# Schematic_ESPHome_P1_Gateway_working_des.net
KiCad netlist of a schematic drawn in EasyEDA
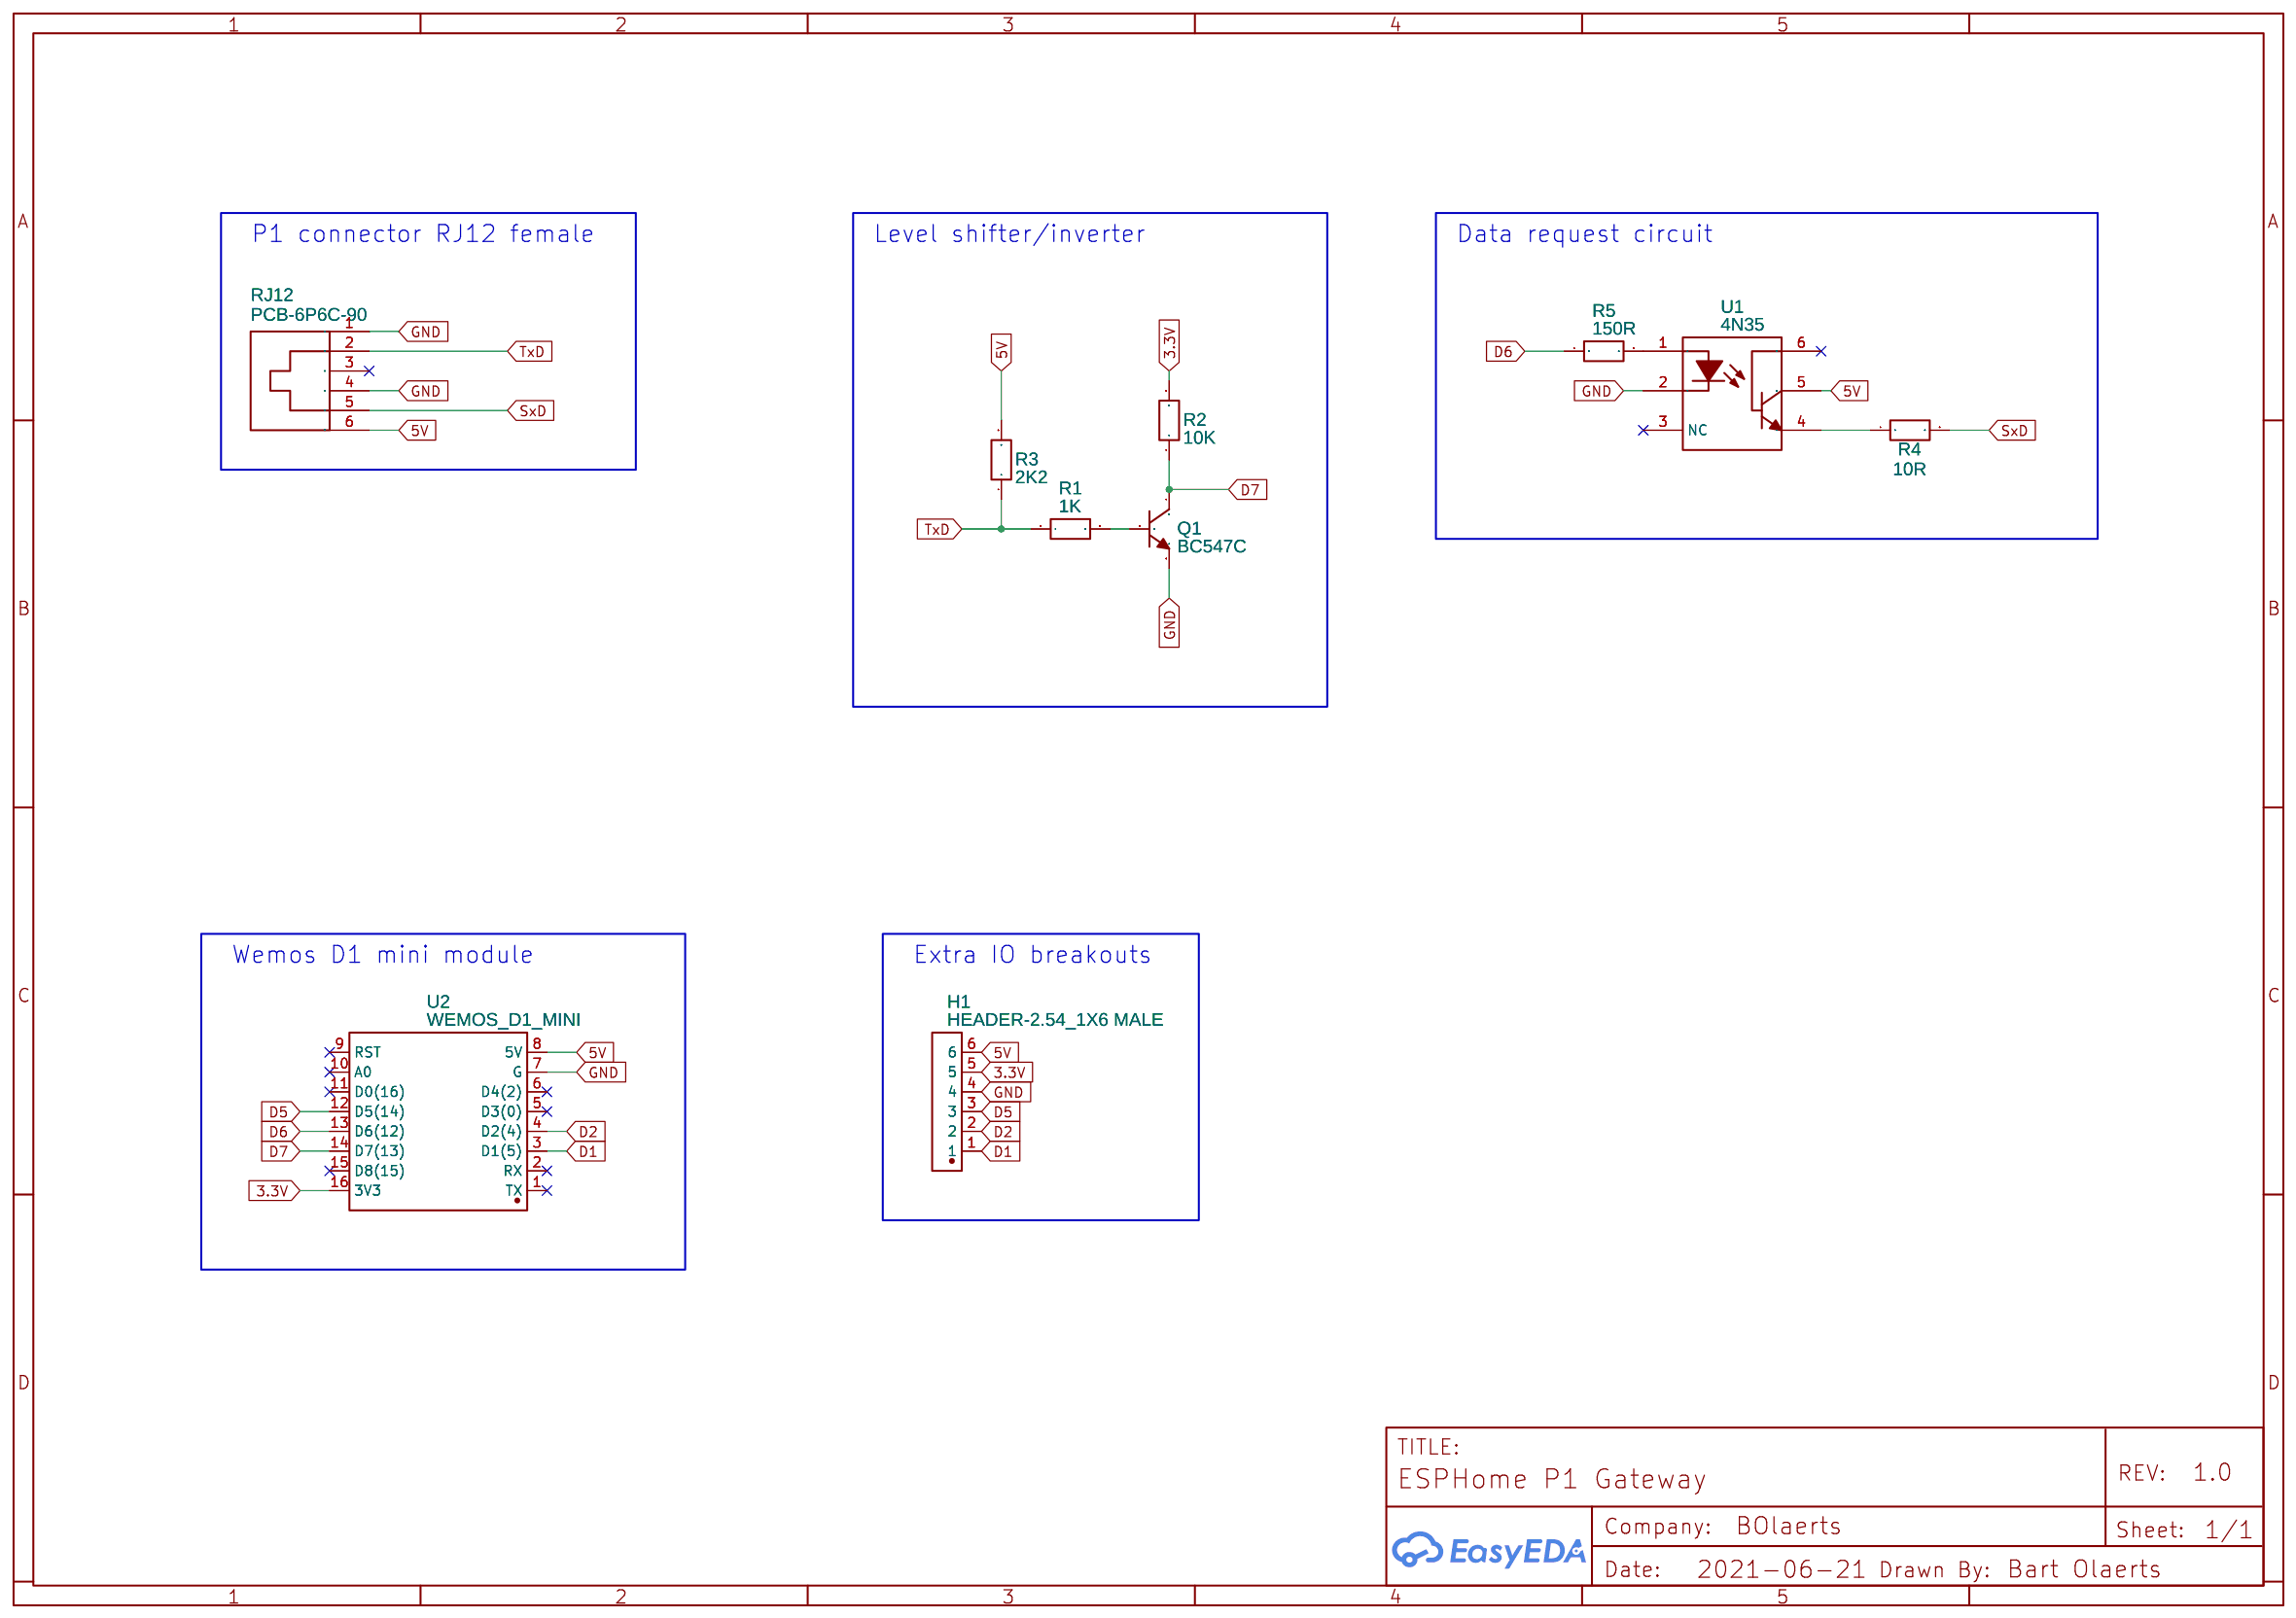
[diagram p0: schematic sheet]

(export (version "E")
  (design (tool "Eeschema 10.0.6"))
  (components
    (comp (ref "H1")
      (value "HEADER-2.54_1X6 MALE")
      (fields
        (field (name "BOM_Manufacturer Part") "Z-211-0411-0021-001")
        (field (name "BOM_Supplier Part") "C152150")
      )
      (libsource (lib "") (part "HEADER-2.54_1X6 MALE"))
    )
    (comp (ref "Q1")
      (value "BC547C")
      (fields (field (name "BOM_Supplier Part") "C713614"))
      (libsource (lib "") (part "BC547C"))
    )
    (comp (ref "R1")
      (value "1K")
      (fields
        (field (name "BOM_Manufacturer Part") "RD 1/2WS 10K J T/B A1")
        (field (name "BOM_Supplier Part") "C433797")
      )
      (libsource (lib "") (part "RD 1/2WS 10K J T/B A1"))
    )
    (comp (ref "R2")
      (value "10K")
      (fields
        (field (name "BOM_Manufacturer Part") "RD 1/2WS 10K J T/B A1")
        (field (name "BOM_Supplier Part") "C433797")
      )
      (libsource (lib "") (part "RD 1/2WS 10K J T/B A1_1"))
    )
    (comp (ref "R3")
      (value "2K2")
      (fields
        (field (name "BOM_Manufacturer Part") "RD 1/2WS 10K J T/B A1")
        (field (name "BOM_Supplier Part") "C433797")
      )
      (libsource (lib "") (part "RD 1/2WS 10K J T/B A1_1"))
    )
    (comp (ref "R4")
      (value "10R")
      (fields
        (field (name "BOM_Manufacturer Part") "RD 1/2WS 10K J T/B A1")
        (field (name "BOM_Supplier Part") "C433797")
      )
      (libsource (lib "") (part "RD 1/2WS 10K J T/B A1"))
    )
    (comp (ref "R5")
      (value "150R")
      (fields
        (field (name "BOM_Manufacturer Part") "RD 1/2WS 10K J T/B A1")
        (field (name "BOM_Supplier Part") "C433797")
      )
      (libsource (lib "") (part "RD 1/2WS 10K J T/B A1"))
    )
    (comp (ref "RJ12")
      (value "PCB-6P6C-90")
      (fields (field (name "BOM_Supplier Part") "C189750"))
      (libsource (lib "") (part "PCB-6P6C-90"))
    )
    (comp (ref "U1")
      (value "4N35")
      (fields (field (name "BOM_Supplier Part") "C57084"))
      (libsource (lib "") (part "4N35"))
    )
    (comp (ref "U2")
      (value "WEMOS_D1_MINI")
      (fields
        (field (name "BOM_Manufacturer Part") "Wemos_D1_mini_Pro4")
        (field (name "BOM_Supplier Part") "C2837266")
      )
      (libsource (lib "") (part "WEMOS_D1_MINI_PRO4"))
    )
  )
  (nets
    (net (code "1") (name "3.3V") (class "Default")
      (node (ref "H1") (pin "5") (pinfunction "5_5") (pintype "unspecified"))
      (node (ref "R2") (pin "2") (pinfunction "2_2") (pintype "unspecified"))
      (node (ref "U2") (pin "16") (pinfunction "3V3_16") (pintype "unspecified"))
    )
    (net (code "2") (name "5V") (class "Default")
      (node (ref "H1") (pin "6") (pinfunction "6_6") (pintype "unspecified"))
      (node (ref "R3") (pin "2") (pinfunction "2_2") (pintype "unspecified"))
      (node (ref "RJ12") (pin "6") (pinfunction "6_6") (pintype "unspecified"))
      (node (ref "U1") (pin "5") (pinfunction "5_5") (pintype "unspecified"))
      (node (ref "U2") (pin "8") (pinfunction "5V_8") (pintype "unspecified"))
    )
    (net (code "3") (name "D1") (class "Default")
      (node (ref "H1") (pin "1") (pinfunction "1_1") (pintype "unspecified"))
      (node (ref "U2") (pin "3") (pinfunction "D1(5)_3") (pintype "unspecified"))
    )
    (net (code "4") (name "D2") (class "Default")
      (node (ref "H1") (pin "2") (pinfunction "2_2") (pintype "unspecified"))
      (node (ref "U2") (pin "4") (pinfunction "D2(4)_4") (pintype "unspecified"))
    )
    (net (code "5") (name "D5") (class "Default")
      (node (ref "H1") (pin "3") (pinfunction "3_3") (pintype "unspecified"))
      (node (ref "U2") (pin "12") (pinfunction "D5(14)_12") (pintype "unspecified"))
    )
    (net (code "6") (name "D6") (class "Default")
      (node (ref "R5") (pin "1") (pinfunction "1_1") (pintype "unspecified"))
      (node (ref "U2") (pin "13") (pinfunction "D6(12)_13") (pintype "unspecified"))
    )
    (net (code "7") (name "D7") (class "Default")
      (node (ref "Q1") (pin "1") (pinfunction "C_1") (pintype "input"))
      (node (ref "R2") (pin "1") (pinfunction "1_1") (pintype "unspecified"))
      (node (ref "U2") (pin "14") (pinfunction "D7(13)_14") (pintype "unspecified"))
    )
    (net (code "8") (name "GND") (class "Default")
      (node (ref "H1") (pin "4") (pinfunction "4_4") (pintype "unspecified"))
      (node (ref "Q1") (pin "3") (pinfunction "E_3") (pintype "input"))
      (node (ref "RJ12") (pin "1") (pinfunction "1_1") (pintype "unspecified"))
      (node (ref "RJ12") (pin "4") (pinfunction "4_4") (pintype "unspecified"))
      (node (ref "U1") (pin "2") (pinfunction "2_2") (pintype "unspecified"))
      (node (ref "U2") (pin "7") (pinfunction "G_7") (pintype "unspecified"))
    )
    (net (code "9") (name "Net-(Q1-B)") (class "Default")
      (node (ref "Q1") (pin "2") (pinfunction "B_2") (pintype "input"))
      (node (ref "R1") (pin "2") (pinfunction "2_2") (pintype "unspecified"))
    )
    (net (code "10") (name "Net-(R4-Pad1)") (class "Default")
      (node (ref "R4") (pin "1") (pinfunction "1_1") (pintype "unspecified"))
      (node (ref "U1") (pin "4") (pinfunction "4_4") (pintype "unspecified"))
    )
    (net (code "11") (name "Net-(R5-Pad2)") (class "Default")
      (node (ref "R5") (pin "2") (pinfunction "2_2") (pintype "unspecified"))
      (node (ref "U1") (pin "1") (pinfunction "1_1") (pintype "unspecified"))
    )
    (net (code "12") (name "SxD") (class "Default")
      (node (ref "R4") (pin "2") (pinfunction "2_2") (pintype "unspecified"))
      (node (ref "RJ12") (pin "5") (pinfunction "5_5") (pintype "unspecified"))
    )
    (net (code "13") (name "TxD") (class "Default")
      (node (ref "R1") (pin "1") (pinfunction "1_1") (pintype "unspecified"))
      (node (ref "R3") (pin "1") (pinfunction "1_1") (pintype "unspecified"))
      (node (ref "RJ12") (pin "2") (pinfunction "2_2") (pintype "unspecified"))
    )
    (net (code "14") (name "unconnected-(RJ12-Pad3)") (class "Default")
      (node (ref "RJ12") (pin "3") (pinfunction "3_3") (pintype "unspecified+no_connect"))
    )
    (net (code "15") (name "unconnected-(U1-NC-Pad3)") (class "Default")
      (node (ref "U1") (pin "3") (pinfunction "NC_3") (pintype "unspecified+no_connect"))
    )
    (net (code "16") (name "unconnected-(U1-Pad6)") (class "Default")
      (node (ref "U1") (pin "6") (pinfunction "6_6") (pintype "unspecified+no_connect"))
    )
    (net (code "17") (name "unconnected-(U2-A0-Pad10)") (class "Default")
      (node (ref "U2") (pin "10") (pinfunction "A0_10") (pintype "unspecified+no_connect"))
    )
    (net (code "18") (name "unconnected-(U2-D0(16)-Pad11)") (class "Default")
      (node (ref "U2") (pin "11") (pinfunction "D0(16)_11") (pintype "unspecified+no_connect"))
    )
    (net (code "19") (name "unconnected-(U2-D3(0)-Pad5)") (class "Default")
      (node (ref "U2") (pin "5") (pinfunction "D3(0)_5") (pintype "unspecified+no_connect"))
    )
    (net (code "20") (name "unconnected-(U2-D4(2)-Pad6)") (class "Default")
      (node (ref "U2") (pin "6") (pinfunction "D4(2)_6") (pintype "unspecified+no_connect"))
    )
    (net (code "21") (name "unconnected-(U2-D8(15)-Pad15)") (class "Default")
      (node (ref "U2") (pin "15") (pinfunction "D8(15)_15") (pintype "unspecified+no_connect"))
    )
    (net (code "22") (name "unconnected-(U2-RST-Pad9)") (class "Default")
      (node (ref "U2") (pin "9") (pinfunction "RST_9") (pintype "unspecified+no_connect"))
    )
    (net (code "23") (name "unconnected-(U2-RX-Pad2)") (class "Default")
      (node (ref "U2") (pin "2") (pinfunction "RX_2") (pintype "unspecified+no_connect"))
    )
    (net (code "24") (name "unconnected-(U2-TX-Pad1)") (class "Default")
      (node (ref "U2") (pin "1") (pinfunction "TX_1") (pintype "unspecified+no_connect"))
    )
  )
)
